# cc2650_rev1-2.net
KiCad netlist of a schematic drawn in EAGLE
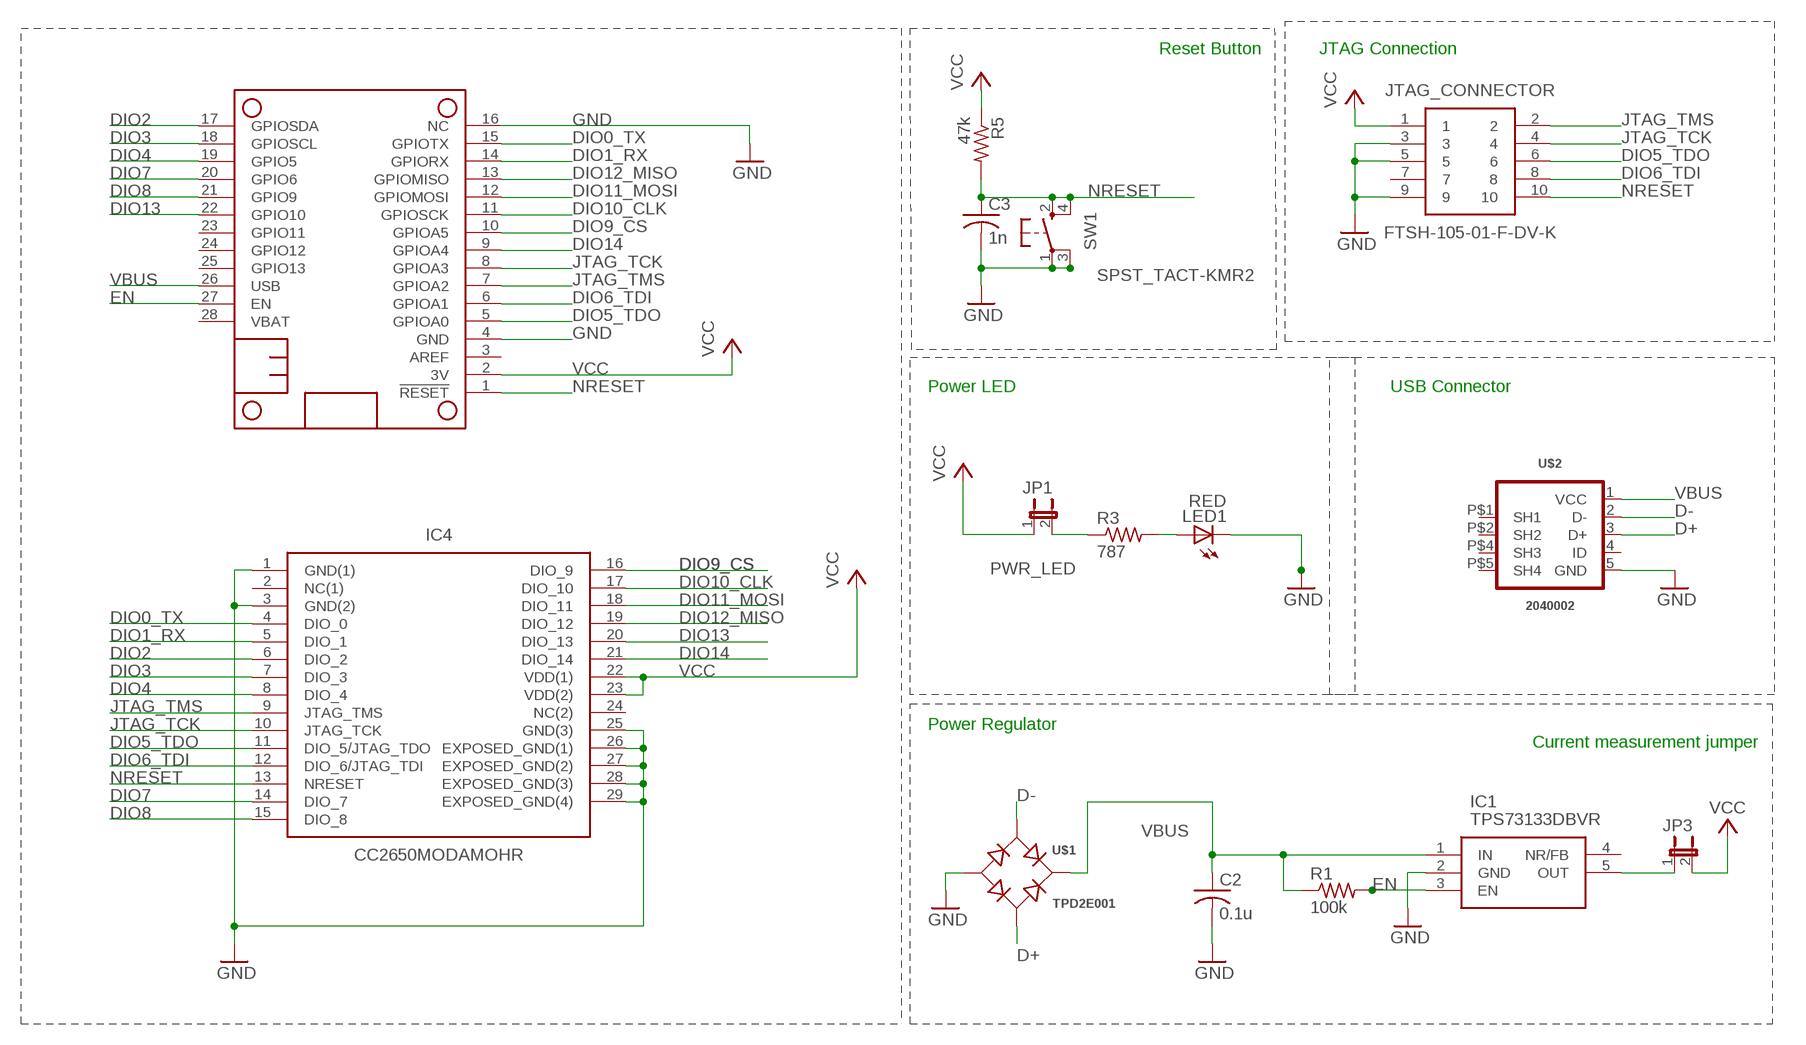
[diagram p0: schematic, sheet 1]
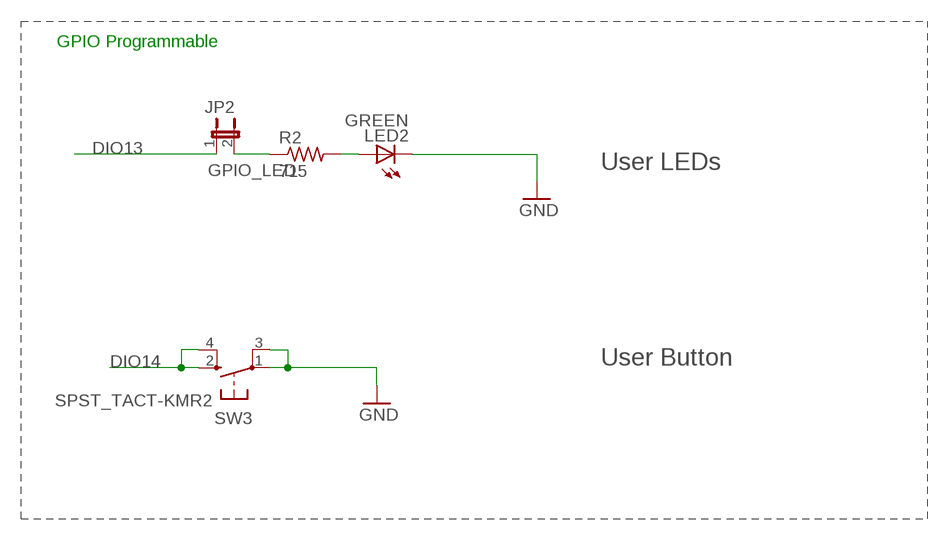
[diagram p1: schematic, sheet 2]

(export (version "E")
  (design (tool "Eeschema 10.0.6"))
  (components
    (comp (ref "C2")
      (value "0.1u")
      (footprint "eagle-import:C1206")
      (fields (field (name "MF") "VISHAY/VITRAMON") (field (name "MPN") "VJ1206Y102KXBAC"))
      (libsource (lib "eagle-import") (part "C-USC1206"))
    )
    (comp (ref "C3")
      (value "1n")
      (footprint "eagle-import:C1206")
      (fields (field (name "MF") "VISHAY/VITRAMON") (field (name "MPN") "VJ1206Y102KXBAC"))
      (libsource (lib "eagle-import") (part "C-USC1206"))
    )
    (comp (ref "IC1")
      (value "TPS73133DBVR")
      (footprint "eagle-import:SOT95P280X145-5N")
      (fields (field (name "RS_PART_NUMBER") "6613970"))
      (libsource (lib "eagle-import") (part "TPS73133DBVR"))
    )
    (comp (ref "IC4")
      (value "CC2650MODAMOHR")
      (footprint "eagle-import:MOH0029A")
      (libsource (lib "eagle-import") (part "CC2650MODAMOHR"))
    )
    (comp (ref "JP1")
      (value "PWR_LED")
      (footprint "eagle-import:JP1M")
      (fields (field (name "MPN") "2211S-02G"))
      (libsource (lib "eagle-import") (part "JP1M"))
    )
    (comp (ref "JP3")
      (value "PWR_LED")
      (footprint "eagle-import:JP1M")
      (fields (field (name "MPN") "2211S-02G"))
      (libsource (lib "eagle-import") (part "JP1M"))
    )
    (comp (ref "JTAG_CONNECTOR")
      (value "FTSH-105-01-F-DV-K")
      (footprint "eagle-import:SAMTEC_FTSH-105-01-L-DV")
      (libsource (lib "eagle-import") (part "FTSH-105-01-F-DV-K"))
    )
    (comp (ref "LED1")
      (value "RED")
      (footprint "eagle-import:CHIPLED_1206")
      (fields (field (name "MPN") "HSMC-C150"))
      (libsource (lib "eagle-import") (part "LEDCHIPLED_1206"))
    )
    (comp (ref "MS1")
      (value "FEATHERWING_NODIM")
      (footprint "eagle-import:FEATHERWING_DIM")
      (libsource (lib "eagle-import") (part "FEATHERWING_NODIM"))
    )
    (comp (ref "R1")
      (value "100k")
      (footprint "eagle-import:R1206")
      (fields (field (name "MPN") "CR1206-FX-4700ELF"))
      (libsource (lib "eagle-import") (part "R-US_R1206"))
    )
    (comp (ref "R3")
      (value "787")
      (footprint "eagle-import:R1206")
      (fields (field (name "MPN") "CR1206-FX-4700ELF"))
      (libsource (lib "eagle-import") (part "R-US_R1206"))
    )
    (comp (ref "R5")
      (value "47k")
      (footprint "eagle-import:R1206")
      (fields (field (name "MF") "VISHAY/DALE") (field (name "MPN") "CRCW120647K0FKTA"))
      (libsource (lib "eagle-import") (part "R-US_R1206"))
    )
    (comp (ref "SW1")
      (value "SPST_TACT-KMR2")
      (footprint "eagle-import:KMR2")
      (fields (field (name "MPN") "KMR241G LFS"))
      (libsource (lib "eagle-import") (part "SPST_TACT-KMR2"))
    )
    (comp (ref "U$1")
      (value "TPD2E001")
      (footprint "eagle-import:SOT-143")
      (libsource (lib "eagle-import") (part "TPD2E001"))
    )
    (comp (ref "U$2")
      (value "2040002")
      (footprint "eagle-import:2040002")
      (libsource (lib "eagle-import") (part "2040002"))
    )
    (comp (ref "JP2")
      (value "GPIO_LED")
      (footprint "eagle-import:JP1M")
      (fields (field (name "MPN") "2211S-02G"))
      (libsource (lib "eagle-import") (part "JP1M"))
    )
    (comp (ref "LED2")
      (value "GREEN")
      (footprint "eagle-import:CHIPLED_1206")
      (fields (field (name "MPN") "HSMC-C150"))
      (libsource (lib "eagle-import") (part "LEDCHIPLED_1206"))
    )
    (comp (ref "R2")
      (value "715")
      (footprint "eagle-import:R1206")
      (fields (field (name "MPN") "CR1206-FX-4700ELF"))
      (libsource (lib "eagle-import") (part "R-US_R1206"))
    )
    (comp (ref "SW3")
      (value "SPST_TACT-KMR2")
      (footprint "eagle-import:KMR2")
      (fields (field (name "MPN") "KMR241G LFS"))
      (libsource (lib "eagle-import") (part "SPST_TACT-KMR2"))
    )
  )
  (nets
    (net (code "1") (name "D+") (class "Default")
      (node (ref "U$1") (pin "3") (pinfunction "AC2_3") (pintype "passive"))
      (node (ref "U$2") (pin "3") (pinfunction "D+_3") (pintype "bidirectional"))
    )
    (net (code "2") (name "D-") (class "Default")
      (node (ref "U$1") (pin "2") (pinfunction "AC1_2") (pintype "passive"))
      (node (ref "U$2") (pin "2") (pinfunction "D-_2") (pintype "bidirectional"))
    )
    (net (code "3") (name "DIO0_TX") (class "Default")
      (node (ref "IC4") (pin "4") (pinfunction "DIO_0_4") (pintype "passive"))
      (node (ref "MS1") (pin "15") (pinfunction "GPIOTX_15") (pintype "bidirectional"))
    )
    (net (code "4") (name "DIO1_RX") (class "Default")
      (node (ref "IC4") (pin "5") (pinfunction "DIO_1_5") (pintype "passive"))
      (node (ref "MS1") (pin "14") (pinfunction "GPIORX_14") (pintype "bidirectional"))
    )
    (net (code "5") (name "DIO2") (class "Default")
      (node (ref "IC4") (pin "6") (pinfunction "DIO_2_6") (pintype "passive"))
      (node (ref "MS1") (pin "17") (pinfunction "GPIOSDA_17") (pintype "bidirectional"))
    )
    (net (code "6") (name "DIO3") (class "Default")
      (node (ref "IC4") (pin "7") (pinfunction "DIO_3_7") (pintype "passive"))
      (node (ref "MS1") (pin "18") (pinfunction "GPIOSCL_18") (pintype "bidirectional"))
    )
    (net (code "7") (name "DIO4") (class "Default")
      (node (ref "IC4") (pin "8") (pinfunction "DIO_4_8") (pintype "passive"))
      (node (ref "MS1") (pin "19") (pinfunction "GPIO5_19") (pintype "bidirectional"))
    )
    (net (code "8") (name "DIO5_TDO") (class "Default")
      (node (ref "IC4") (pin "11") (pinfunction "DIO_5/JTAG_TDO_11") (pintype "passive"))
      (node (ref "JTAG_CONNECTOR") (pin "6") (pinfunction "6_6") (pintype "passive"))
      (node (ref "MS1") (pin "5") (pinfunction "GPIOA0_5") (pintype "bidirectional"))
    )
    (net (code "9") (name "DIO6_TDI") (class "Default")
      (node (ref "IC4") (pin "12") (pinfunction "DIO_6/JTAG_TDI_12") (pintype "passive"))
      (node (ref "JTAG_CONNECTOR") (pin "8") (pinfunction "8_8") (pintype "passive"))
      (node (ref "MS1") (pin "6") (pinfunction "GPIOA1_6") (pintype "bidirectional"))
    )
    (net (code "10") (name "DIO7") (class "Default")
      (node (ref "IC4") (pin "14") (pinfunction "DIO_7_14") (pintype "passive"))
      (node (ref "MS1") (pin "20") (pinfunction "GPIO6_20") (pintype "bidirectional"))
    )
    (net (code "11") (name "DIO8") (class "Default")
      (node (ref "IC4") (pin "15") (pinfunction "DIO_8_15") (pintype "passive"))
      (node (ref "MS1") (pin "21") (pinfunction "GPIO9_21") (pintype "bidirectional"))
    )
    (net (code "12") (name "DIO9_CS") (class "Default")
      (node (ref "IC4") (pin "16") (pinfunction "DIO_9_16") (pintype "passive"))
      (node (ref "MS1") (pin "10") (pinfunction "GPIOA5_10") (pintype "bidirectional"))
    )
    (net (code "13") (name "DIO10_CLK") (class "Default")
      (node (ref "IC4") (pin "17") (pinfunction "DIO_10_17") (pintype "passive"))
      (node (ref "MS1") (pin "11") (pinfunction "GPIOSCK_11") (pintype "bidirectional"))
    )
    (net (code "14") (name "DIO11_MOSI") (class "Default")
      (node (ref "IC4") (pin "18") (pinfunction "DIO_11_18") (pintype "passive"))
      (node (ref "MS1") (pin "12") (pinfunction "GPIOMOSI_12") (pintype "bidirectional"))
    )
    (net (code "15") (name "DIO12_MISO") (class "Default")
      (node (ref "IC4") (pin "19") (pinfunction "DIO_12_19") (pintype "passive"))
      (node (ref "MS1") (pin "13") (pinfunction "GPIOMISO_13") (pintype "bidirectional"))
    )
    (net (code "16") (name "DIO13") (class "Default")
      (node (ref "IC4") (pin "20") (pinfunction "DIO_13_20") (pintype "passive"))
      (node (ref "JP2") (pin "1") (pinfunction "1_1") (pintype "passive"))
      (node (ref "MS1") (pin "22") (pinfunction "GPIO10_22") (pintype "bidirectional"))
    )
    (net (code "17") (name "DIO14") (class "Default")
      (node (ref "IC4") (pin "21") (pinfunction "DIO_14_21") (pintype "passive"))
      (node (ref "MS1") (pin "9") (pinfunction "GPIOA4_9") (pintype "bidirectional"))
      (node (ref "SW3") (pin "2") (pinfunction "S_2") (pintype "passive"))
      (node (ref "SW3") (pin "4") (pinfunction "S1_4") (pintype "passive"))
    )
    (net (code "18") (name "EN") (class "Default")
      (node (ref "IC1") (pin "3") (pinfunction "EN_3") (pintype "input"))
      (node (ref "MS1") (pin "27") (pinfunction "EN_27") (pintype "passive"))
      (node (ref "R1") (pin "2") (pinfunction "2_2") (pintype "passive"))
    )
    (net (code "19") (name "GND") (class "Default")
      (node (ref "C2") (pin "2") (pinfunction "2_2") (pintype "passive"))
      (node (ref "C3") (pin "2") (pinfunction "2_2") (pintype "passive"))
      (node (ref "IC1") (pin "2") (pinfunction "GND_2") (pintype "input"))
      (node (ref "IC4") (pin "1") (pinfunction "GND(1)_1") (pintype "passive"))
      (node (ref "IC4") (pin "25") (pinfunction "GND(3)_25") (pintype "passive"))
      (node (ref "IC4") (pin "26") (pinfunction "EXPOSED_GND(1)_26") (pintype "passive"))
      (node (ref "IC4") (pin "27") (pinfunction "EXPOSED_GND(2)_27") (pintype "passive"))
      (node (ref "IC4") (pin "28") (pinfunction "EXPOSED_GND(3)_28") (pintype "passive"))
      (node (ref "IC4") (pin "29") (pinfunction "EXPOSED_GND(4)_29") (pintype "passive"))
      (node (ref "IC4") (pin "3") (pinfunction "GND(2)_3") (pintype "passive"))
      (node (ref "JTAG_CONNECTOR") (pin "3") (pinfunction "3_3") (pintype "passive"))
      (node (ref "JTAG_CONNECTOR") (pin "5") (pinfunction "5_5") (pintype "passive"))
      (node (ref "JTAG_CONNECTOR") (pin "9") (pinfunction "9_9") (pintype "passive"))
      (node (ref "LED1") (pin "C") (pinfunction "C_C") (pintype "passive"))
      (node (ref "LED2") (pin "C") (pinfunction "C_C") (pintype "passive"))
      (node (ref "MS1") (pin "16") (pinfunction "NC_16") (pintype "passive"))
      (node (ref "MS1") (pin "4") (pinfunction "GND_4") (pintype "power_in"))
      (node (ref "SW1") (pin "1") (pinfunction "P_1") (pintype "passive"))
      (node (ref "SW1") (pin "3") (pinfunction "P1_3") (pintype "passive"))
      (node (ref "SW3") (pin "1") (pinfunction "P_1") (pintype "passive"))
      (node (ref "SW3") (pin "3") (pinfunction "P1_3") (pintype "passive"))
      (node (ref "U$1") (pin "1") (pinfunction "-_1") (pintype "passive"))
      (node (ref "U$2") (pin "5") (pinfunction "GND_5") (pintype "bidirectional"))
    )
    (net (code "20") (name "JTAG_TCK") (class "Default")
      (node (ref "IC4") (pin "10") (pinfunction "JTAG_TCK_10") (pintype "passive"))
      (node (ref "JTAG_CONNECTOR") (pin "4") (pinfunction "4_4") (pintype "passive"))
      (node (ref "MS1") (pin "8") (pinfunction "GPIOA3_8") (pintype "bidirectional"))
    )
    (net (code "21") (name "JTAG_TMS") (class "Default")
      (node (ref "IC4") (pin "9") (pinfunction "JTAG_TMS_9") (pintype "passive"))
      (node (ref "JTAG_CONNECTOR") (pin "2") (pinfunction "2_2") (pintype "passive"))
      (node (ref "MS1") (pin "7") (pinfunction "GPIOA2_7") (pintype "bidirectional"))
    )
    (net (code "22") (name "NRESET") (class "Default")
      (node (ref "C3") (pin "1") (pinfunction "1_1") (pintype "passive"))
      (node (ref "IC4") (pin "13") (pinfunction "NRESET_13") (pintype "passive"))
      (node (ref "JTAG_CONNECTOR") (pin "10") (pinfunction "10_10") (pintype "passive"))
      (node (ref "MS1") (pin "1") (pinfunction "~{RESET}_1") (pintype "input"))
      (node (ref "R5") (pin "2") (pinfunction "2_2") (pintype "passive"))
      (node (ref "SW1") (pin "2") (pinfunction "S_2") (pintype "passive"))
      (node (ref "SW1") (pin "4") (pinfunction "S1_4") (pintype "passive"))
    )
    (net (code "23") (name "Net-(IC1-OUT)") (class "Default")
      (node (ref "IC1") (pin "5") (pinfunction "OUT_5") (pintype "input"))
      (node (ref "JP3") (pin "1") (pinfunction "1_1") (pintype "passive"))
    )
    (net (code "24") (name "Net-(JP1-Pad2)") (class "Default")
      (node (ref "JP1") (pin "2") (pinfunction "2_2") (pintype "passive"))
      (node (ref "R3") (pin "1") (pinfunction "1_1") (pintype "passive"))
    )
    (net (code "25") (name "Net-(JP2-Pad2)") (class "Default")
      (node (ref "JP2") (pin "2") (pinfunction "2_2") (pintype "passive"))
      (node (ref "R2") (pin "1") (pinfunction "1_1") (pintype "passive"))
    )
    (net (code "26") (name "Net-(LED1-PadA)") (class "Default")
      (node (ref "LED1") (pin "A") (pinfunction "A_A") (pintype "passive"))
      (node (ref "R3") (pin "2") (pinfunction "2_2") (pintype "passive"))
    )
    (net (code "27") (name "Net-(LED2-PadA)") (class "Default")
      (node (ref "LED2") (pin "A") (pinfunction "A_A") (pintype "passive"))
      (node (ref "R2") (pin "2") (pinfunction "2_2") (pintype "passive"))
    )
    (net (code "28") (name "VBAT") (class "Default")
      (node (ref "MS1") (pin "28") (pinfunction "VBAT_28") (pintype "power_in"))
    )
    (net (code "29") (name "VBUS") (class "Default")
      (node (ref "C2") (pin "1") (pinfunction "1_1") (pintype "passive"))
      (node (ref "IC1") (pin "1") (pinfunction "IN_1") (pintype "input"))
      (node (ref "MS1") (pin "26") (pinfunction "USB_26") (pintype "power_in"))
      (node (ref "R1") (pin "1") (pinfunction "1_1") (pintype "passive"))
      (node (ref "U$1") (pin "4") (pinfunction "+_4") (pintype "passive"))
      (node (ref "U$2") (pin "1") (pinfunction "VCC_1") (pintype "bidirectional"))
    )
    (net (code "30") (name "VCC") (class "Default")
      (node (ref "IC4") (pin "22") (pinfunction "VDD(1)_22") (pintype "passive"))
      (node (ref "IC4") (pin "23") (pinfunction "VDD(2)_23") (pintype "passive"))
      (node (ref "JP1") (pin "1") (pinfunction "1_1") (pintype "passive"))
      (node (ref "JP3") (pin "2") (pinfunction "2_2") (pintype "passive"))
      (node (ref "JTAG_CONNECTOR") (pin "1") (pinfunction "1_1") (pintype "passive"))
      (node (ref "MS1") (pin "2") (pinfunction "3V_2") (pintype "power_in"))
      (node (ref "R5") (pin "1") (pinfunction "1_1") (pintype "passive"))
    )
    (net (code "31") (name "unconnected-(IC1-NR{slash}FB-Pad4)") (class "Default")
      (node (ref "IC1") (pin "4") (pinfunction "NR/FB_4") (pintype "input"))
    )
    (net (code "32") (name "unconnected-(IC4-NC(1)-Pad2)") (class "Default")
      (node (ref "IC4") (pin "2") (pinfunction "NC(1)_2") (pintype "passive"))
    )
    (net (code "33") (name "unconnected-(IC4-NC(2)-Pad24)") (class "Default")
      (node (ref "IC4") (pin "24") (pinfunction "NC(2)_24") (pintype "passive"))
    )
    (net (code "34") (name "unconnected-(JTAG_CONNECTOR-Pad7)") (class "Default")
      (node (ref "JTAG_CONNECTOR") (pin "7") (pinfunction "7_7") (pintype "passive"))
    )
    (net (code "35") (name "unconnected-(MS1-AREF-Pad3)") (class "Default")
      (node (ref "MS1") (pin "3") (pinfunction "AREF_3") (pintype "passive"))
    )
    (net (code "36") (name "unconnected-(MS1-GPIO11-Pad23)") (class "Default")
      (node (ref "MS1") (pin "23") (pinfunction "GPIO11_23") (pintype "bidirectional"))
    )
    (net (code "37") (name "unconnected-(MS1-GPIO12-Pad24)") (class "Default")
      (node (ref "MS1") (pin "24") (pinfunction "GPIO12_24") (pintype "bidirectional"))
    )
    (net (code "38") (name "unconnected-(MS1-GPIO13-Pad25)") (class "Default")
      (node (ref "MS1") (pin "25") (pinfunction "GPIO13_25") (pintype "bidirectional"))
    )
    (net (code "39") (name "unconnected-(U$2-ID-Pad4)") (class "Default")
      (node (ref "U$2") (pin "4") (pinfunction "ID_4") (pintype "bidirectional"))
    )
    (net (code "40") (name "unconnected-(U$2-SH1-PadP$1)") (class "Default")
      (node (ref "U$2") (pin "P$1") (pinfunction "SH1_P$1") (pintype "no_connect"))
    )
    (net (code "41") (name "unconnected-(U$2-SH2-PadP$2)") (class "Default")
      (node (ref "U$2") (pin "P$2") (pinfunction "SH2_P$2") (pintype "no_connect"))
    )
    (net (code "42") (name "unconnected-(U$2-SH3-PadP$4)") (class "Default")
      (node (ref "U$2") (pin "P$4") (pinfunction "SH3_P$4") (pintype "no_connect"))
    )
    (net (code "43") (name "unconnected-(U$2-SH4-PadP$5)") (class "Default")
      (node (ref "U$2") (pin "P$5") (pinfunction "SH4_P$5") (pintype "no_connect"))
    )
  )
)
